# Viper22PS.net
KiCad netlist of a schematic drawn in Altium Designer
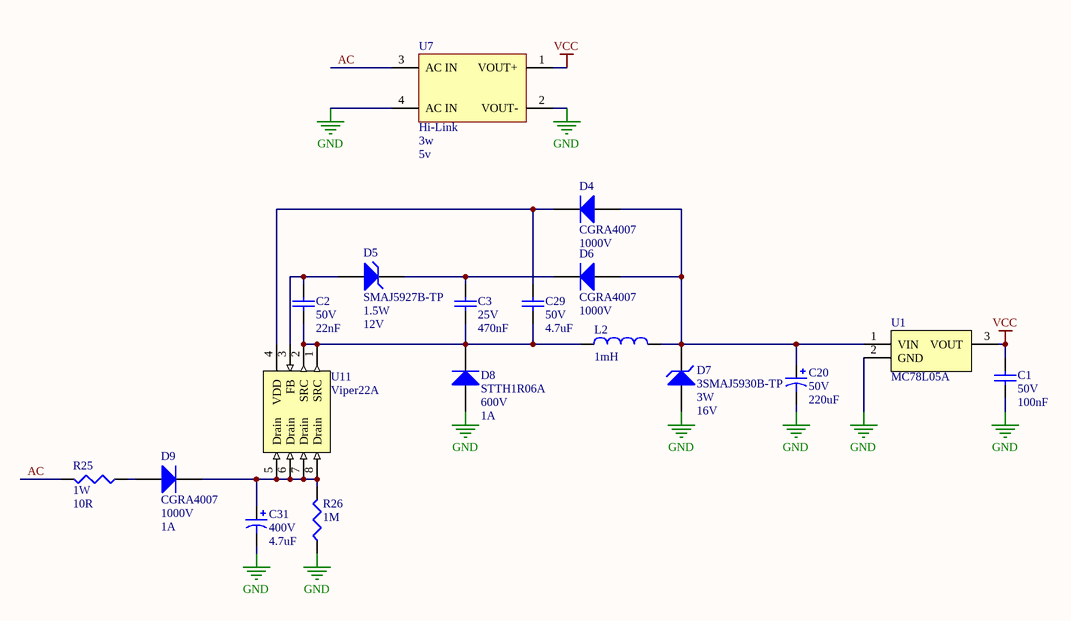
[diagram p0: Viper22PS.SchDoc]

(export (version "E")
  (design (tool "Eeschema 10.0.6"))
  (components
    (comp (ref "C1")
      (value "100nF")
      (footprint "CC0603")
      (description "Capacitor (Semiconductor SIM Model)")
      (fields (field (name "TENSÃO") "50V") (field (name "Comment") "Capacitor Cerâmico"))
      (libsource (lib "NavarroCAP") (part "Cap 100nF 50V 0603 X7R"))
    )
    (comp (ref "C2")
      (value "22nF")
      (footprint "CC0603")
      (description "Capacitor (Semiconductor SIM Model)")
      (fields (field (name "TENSÃO") "50V") (field (name "Comment") "Capacitor Cerâmico"))
      (libsource (lib "TecnocladeCAP") (part "Cap 22nF 50V 0603 X7R"))
    )
    (comp (ref "C3")
      (value "470nF")
      (footprint "CC0603")
      (description "Capacitor (Semiconductor SIM Model)")
      (fields (field (name "TENSÃO") "25V") (field (name "Comment") "Capacitor Cerâmico"))
      (libsource (lib "TecnocladeCAP") (part "Cap 470nF 25V 0603 X7R"))
    )
    (comp (ref "C20")
      (value "220uF")
      (footprint "CPOLRAD10X20")
      (description "Polarized Capacitor")
      (fields (field (name "TENSÃO") "50V") (field (name "Comment") "Capacitor Aluminio"))
      (libsource (lib "NavarroCAP") (part "PCap 220uF 50V CPOLRAD10X20 LOESR"))
    )
    (comp (ref "C29")
      (value "4.7uF")
      (footprint "CC0805")
      (description "Capacitor (Semiconductor SIM Model)")
      (fields (field (name "TENSÃO") "50V") (field (name "Comment") "Capacitor Cerâmico"))
      (libsource (lib "TecnocladeCAP") (part "Cap 4.7uF 50V 0805 X5R"))
    )
    (comp (ref "C31")
      (value "4.7uF")
      (footprint "CPOLRAD8X12")
      (description "Polarized Capacitor (Radial)")
      (fields (field (name "TENSÃO") "400V") (field (name "Comment") "Capacitor Eletrolítico"))
      (libsource (lib "TecnocladeCAP") (part "PCap 4.7uF 400V 8d.x12h."))
    )
    (comp (ref "D4")
      (value "CGRA4007")
      (footprint "SMA")
      (description "1 Amp General Purpose Rectifier")
      (fields (field (name "TENSÃO") "1000V"))
      (libsource (lib "TecnocladeSEMI") (part "DP 1000V 1A SMA"))
    )
    (comp (ref "D5")
      (value "SMAJ5927B-TP")
      (footprint "SMA")
      (description "Zener Diode")
      (fields (field (name "POTÊNCIA") "1.5W") (field (name "TENSÃO") "12V"))
      (libsource (lib "TecnocladeSEMI") (part "DZ 12V 1.5W SMA"))
    )
    (comp (ref "D6")
      (value "CGRA4007")
      (footprint "SMA")
      (description "1 Amp General Purpose Rectifier")
      (fields (field (name "TENSÃO") "1000V"))
      (libsource (lib "TecnocladeSEMI") (part "DP 1000V 1A SMA"))
    )
    (comp (ref "D7")
      (value "3SMAJ5930B-TP")
      (footprint "SMA")
      (description "Zener Diode")
      (fields (field (name "POTÊNCIA") "3W") (field (name "TENSÃO") "16V"))
      (libsource (lib "TecnocladeSEMI") (part "DZ 16V 3W SMA"))
    )
    (comp (ref "D8")
      (value "STTH1R06A")
      (footprint "SMA")
      (description "1 Amp General Purpose Rectifier")
      (fields (field (name "TENSÃO") "600V") (field (name "CORRENTE") "1A"))
      (libsource (lib "TecnocladeSEMI") (part "DP 600V 1A SMA (2)"))
    )
    (comp (ref "D9")
      (value "CGRA4007")
      (footprint "SMA")
      (description "1 Amp General Purpose Rectifier")
      (fields (field (name "TENSÃO") "1000V") (field (name "CORRENTE") "1A"))
      (libsource (lib "TecnocladeSEMI") (part "DP 1000V 1A SMA"))
    )
    (comp (ref "L2")
      (value "1mH")
      (footprint "Indutor_Viper")
      (description "Inductor Shielded")
      (fields (field (name "Comment") "Indutor"))
      (libsource (lib "TecnocladeIND") (part "Ind 1mH 1211 70mA"))
    )
    (comp (ref "R25")
      (value "10R")
      (footprint "CC1206")
      (description "Fusible Thin Film Chip Resistors")
      (fields (field (name "POTÊNCIA") "1W") (field (name "Comment") "Resistor"))
      (libsource (lib "TecnocladeRES") (part "THRes 10R 5% 1020 1W"))
    )
    (comp (ref "R26")
      (value "1M")
      (footprint "CC1206")
      (description "Resistor")
      (libsource (lib "TecnocladeRES") (part "Res 1M 1% 1206 1/4W"))
    )
    (comp (ref "U1")
      (value "MC78L05A")
      (footprint "SOT-89-3N")
      (description "Regulador Linear 5V")
      (libsource (lib "Navarro") (part "MC78L05"))
    )
    (comp (ref "U7")
      (value "Hi-Link")
      (footprint "Fonte-HILINK")
      (description "Fonte chaveada isolada")
      (fields (field (name "POTÊNCIA") "3w") (field (name "TENSÃO") "5v"))
      (libsource (lib "Navarro") (part "Fonte Hi-Link"))
    )
    (comp (ref "U11")
      (value "Viper22A")
      (footprint "DIP8")
      (description "Low power OFF-line SMPS primary switcher")
      (libsource (lib "Navarro") (part "Viper22A"))
    )
  )
  (nets
    (net (code "1") (name "/AC") (class "Default")
      (node (ref "R25") (pin "2") (pinfunction "2_2") (pintype "passive"))
      (node (ref "U7") (pin "3") (pinfunction "AC_IN_3") (pintype "power_in"))
    )
    (net (code "2") (name "GND") (class "Default")
      (node (ref "C1") (pin "1") (pinfunction "1_1") (pintype "passive"))
      (node (ref "C20") (pin "2") (pinfunction "2_2") (pintype "passive"))
      (node (ref "C31") (pin "2") (pinfunction "2_2") (pintype "passive"))
      (node (ref "D7") (pin "1") (pinfunction "A_1") (pintype "passive"))
      (node (ref "D8") (pin "1") (pinfunction "A_1") (pintype "passive"))
      (node (ref "R26") (pin "1") (pinfunction "1_1") (pintype "passive"))
      (node (ref "U1") (pin "2") (pinfunction "GND_2") (pintype "power_in"))
      (node (ref "U7") (pin "2") (pinfunction "VOUT-_2") (pintype "power_in"))
      (node (ref "U7") (pin "4") (pinfunction "AC_IN_4") (pintype "power_in"))
    )
    (net (code "3") (name "Net-(D4-A)") (class "Default")
      (node (ref "C20") (pin "1") (pinfunction "1_1") (pintype "passive"))
      (node (ref "D4") (pin "1") (pinfunction "A_1") (pintype "passive"))
      (node (ref "D6") (pin "1") (pinfunction "A_1") (pintype "passive"))
      (node (ref "D7") (pin "2") (pinfunction "K_2") (pintype "passive"))
      (node (ref "L2") (pin "2") (pinfunction "2_2") (pintype "passive"))
      (node (ref "U1") (pin "1") (pinfunction "VIN_1") (pintype "power_in"))
    )
    (net (code "4") (name "Net-(D4-K)") (class "Default")
      (node (ref "C29") (pin "2") (pinfunction "2_2") (pintype "passive"))
      (node (ref "D4") (pin "2") (pinfunction "K_2") (pintype "passive"))
      (node (ref "U11") (pin "4") (pinfunction "VDD_4") (pintype "power_in"))
    )
    (net (code "5") (name "Net-(D5-A)") (class "Default")
      (node (ref "C2") (pin "2") (pinfunction "2_2") (pintype "passive"))
      (node (ref "D5") (pin "1") (pinfunction "A_1") (pintype "passive"))
      (node (ref "U11") (pin "3") (pinfunction "FB_3") (pintype "input"))
    )
    (net (code "6") (name "Net-(D5-K)") (class "Default")
      (node (ref "C3") (pin "2") (pinfunction "2_2") (pintype "passive"))
      (node (ref "D5") (pin "2") (pinfunction "K_2") (pintype "passive"))
      (node (ref "D6") (pin "2") (pinfunction "K_2") (pintype "passive"))
    )
    (net (code "7") (name "Net-(D8-K)") (class "Default")
      (node (ref "C2") (pin "1") (pinfunction "1_1") (pintype "passive"))
      (node (ref "C29") (pin "1") (pinfunction "1_1") (pintype "passive"))
      (node (ref "C3") (pin "1") (pinfunction "1_1") (pintype "passive"))
      (node (ref "D8") (pin "2") (pinfunction "K_2") (pintype "passive"))
      (node (ref "L2") (pin "1") (pinfunction "1_1") (pintype "passive"))
      (node (ref "U11") (pin "1") (pinfunction "SRC_1") (pintype "output"))
      (node (ref "U11") (pin "2") (pinfunction "SRC_2") (pintype "output"))
    )
    (net (code "8") (name "Net-(D9-A)") (class "Default")
      (node (ref "D9") (pin "1") (pinfunction "A_1") (pintype "passive"))
      (node (ref "R25") (pin "1") (pinfunction "1_1") (pintype "passive"))
    )
    (net (code "9") (name "Net-(D9-K)") (class "Default")
      (node (ref "C31") (pin "1") (pinfunction "1_1") (pintype "passive"))
      (node (ref "D9") (pin "2") (pinfunction "K_2") (pintype "passive"))
      (node (ref "R26") (pin "2") (pinfunction "2_2") (pintype "passive"))
      (node (ref "U11") (pin "5") (pinfunction "Drain_5") (pintype "input"))
      (node (ref "U11") (pin "6") (pinfunction "Drain_6") (pintype "input"))
      (node (ref "U11") (pin "7") (pinfunction "Drain_7") (pintype "input"))
      (node (ref "U11") (pin "8") (pinfunction "Drain_8") (pintype "input"))
    )
    (net (code "10") (name "VCC") (class "Default")
      (node (ref "C1") (pin "2") (pinfunction "2_2") (pintype "passive"))
      (node (ref "U1") (pin "3") (pinfunction "VOUT_3") (pintype "power_in"))
      (node (ref "U7") (pin "1") (pinfunction "VOUT+_1") (pintype "power_in"))
    )
  )
)
